# Arduino_Shield_RC_Controller.net
KiCad netlist of a schematic drawn in EAGLE
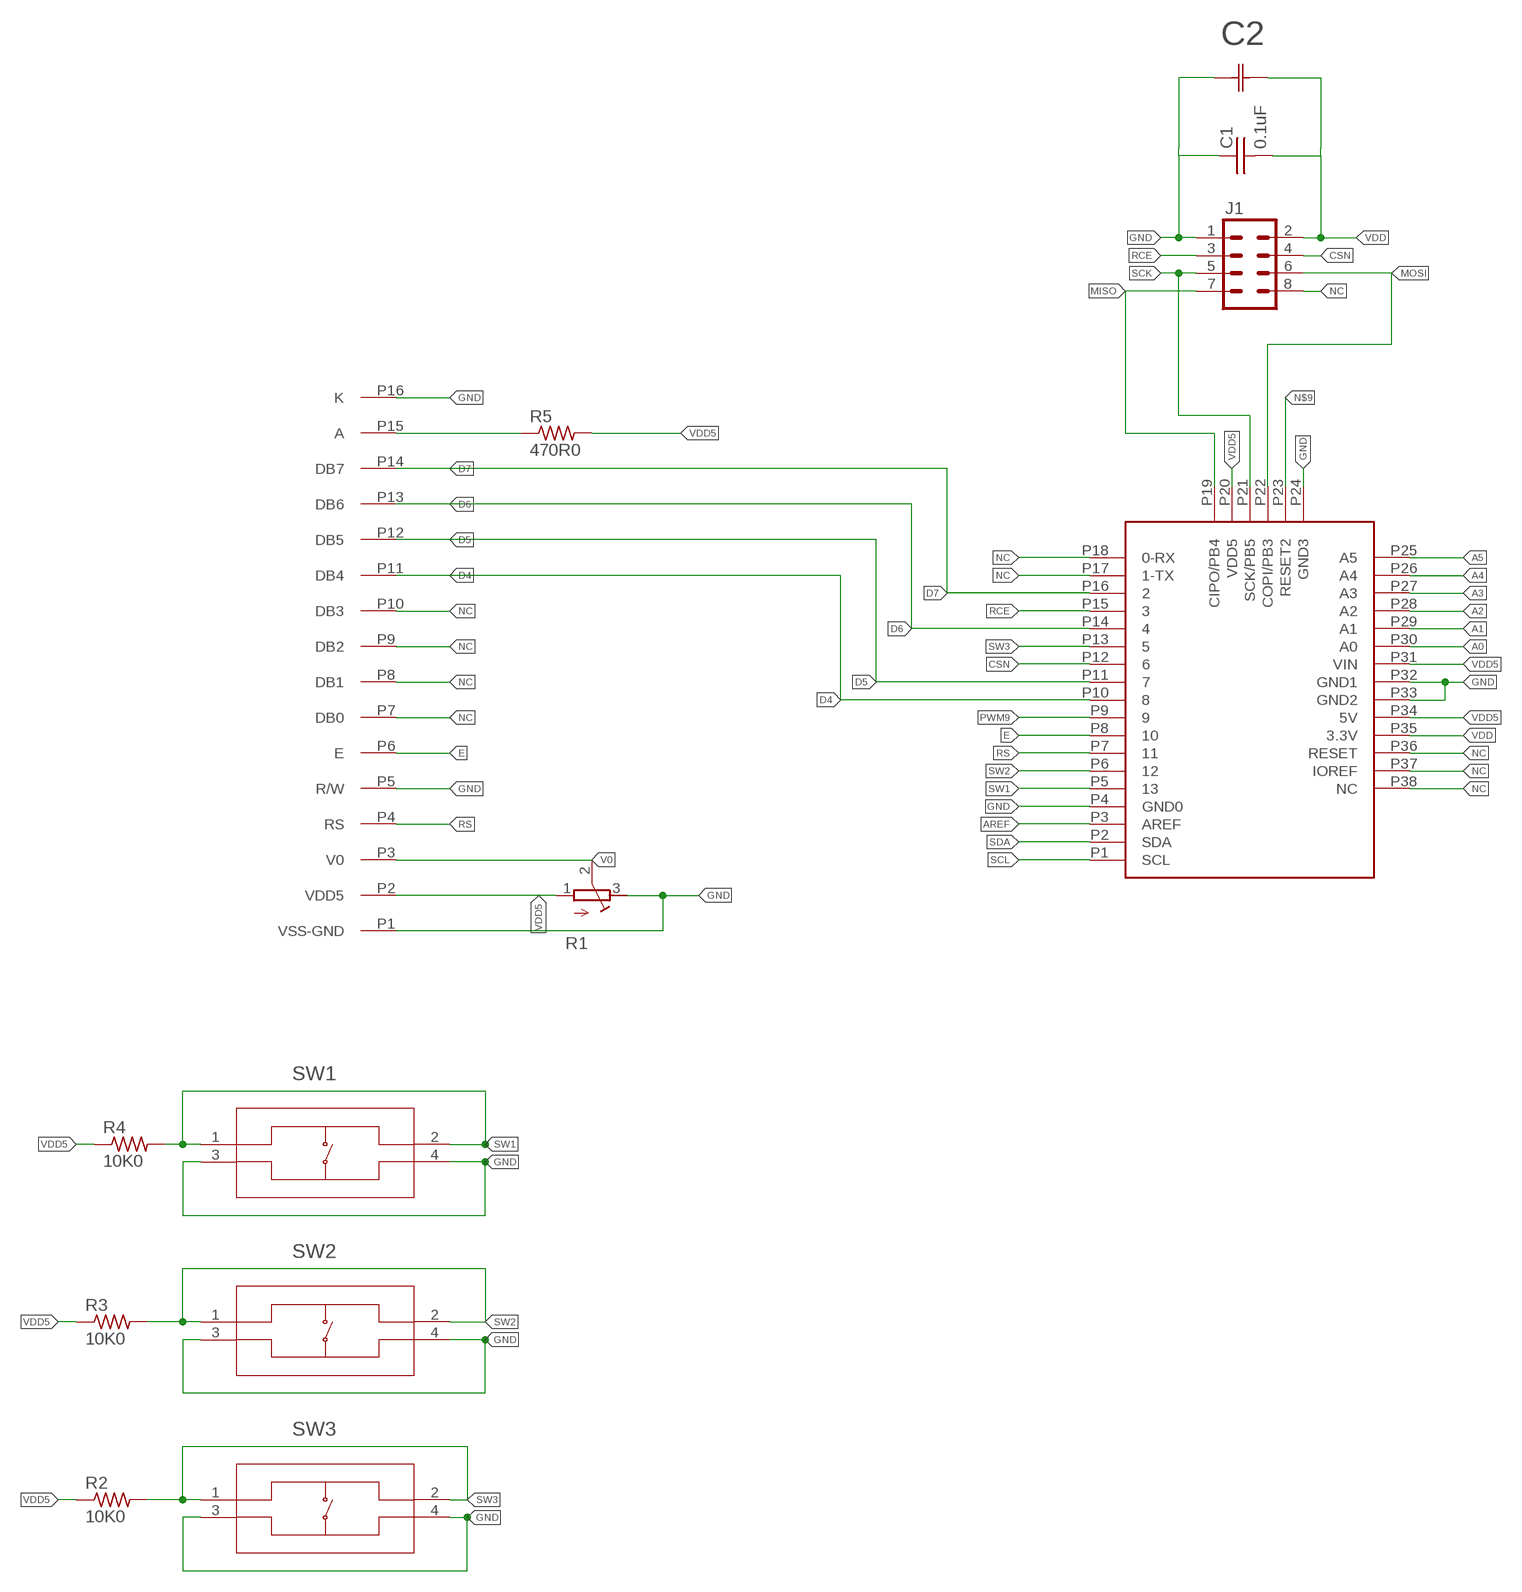
[diagram p0: schematic, sheet 1]

(export (version "E")
  (design (tool "Eeschema 10.0.6"))
  (components
    (comp (ref "AR1")
      (value "ARDUINO_R3")
      (footprint "eagle-import:ARDUINO_R3")
      (libsource (lib "eagle-import") (part "ARDUINO_R3"))
    )
    (comp (ref "C1")
      (value "0.1uF")
      (footprint "eagle-import:0402")
      (fields (field (name "PARTNO") "CL05F104ZO5NNNC"))
      (libsource (lib "eagle-import") (part "C_0402_0.1UF"))
    )
    (comp (ref "C2")
      (value "CAP_470UF_RAD_TH")
      (footprint "eagle-import:CAP_YX_10X16_RUB")
      (fields
        (field (name "MANUFACTURER_PART_NUMBER") "35ZLH470MEFC10X16")
        (field (name "COPYRIGHT") "Copyright (C) 2023 Ultra Librarian. All rights reserved.")
      )
      (libsource (lib "eagle-import") (part "CAP_470UF_RAD_TH"))
    )
    (comp (ref "J1")
      (value "CONN_04X2")
      (footprint "eagle-import:2X4")
      (libsource (lib "eagle-import") (part "CONN_04X2"))
    )
    (comp (ref "LCD1")
      (value "ADM1602K")
      (footprint "eagle-import:ADM1602K")
      (libsource (lib "eagle-import") (part "ADM1602K"))
    )
    (comp (ref "R1")
      (value "R-TRIMM3103")
      (footprint "eagle-import:RTRIM3103")
      (libsource (lib "eagle-import") (part "R-TRIMM3103"))
    )
    (comp (ref "R2")
      (value "10K0")
      (footprint "eagle-import:0402")
      (fields (field (name "PARTNO") "RMCF0402JT10K0"))
      (libsource (lib "eagle-import") (part "R_0402_10K0"))
    )
    (comp (ref "R3")
      (value "10K0")
      (footprint "eagle-import:0402")
      (fields (field (name "PARTNO") "RMCF0402JT10K0"))
      (libsource (lib "eagle-import") (part "R_0402_10K0"))
    )
    (comp (ref "R4")
      (value "10K0")
      (footprint "eagle-import:0402")
      (fields (field (name "PARTNO") "RMCF0402JT10K0"))
      (libsource (lib "eagle-import") (part "R_0402_10K0"))
    )
    (comp (ref "R5")
      (value "470R0")
      (footprint "eagle-import:0402")
      (fields (field (name "PARTNO") "RMCF0402JT470R"))
      (libsource (lib "eagle-import") (part "R_0402_470R0"))
    )
    (comp (ref "SW1")
      (value "PTS810SJG250SMTRLFS")
      (footprint "eagle-import:PTS810")
      (fields (field (name "COPYRIGHT") "Copyright (C) 2018 Accelerated Designs. All rights reserved"))
      (libsource (lib "eagle-import") (part "PTS810SJG250SMTRLFS"))
    )
    (comp (ref "SW2")
      (value "PTS810SJG250SMTRLFS")
      (footprint "eagle-import:PTS810")
      (fields (field (name "COPYRIGHT") "Copyright (C) 2018 Accelerated Designs. All rights reserved"))
      (libsource (lib "eagle-import") (part "PTS810SJG250SMTRLFS"))
    )
    (comp (ref "SW3")
      (value "PTS810SJG250SMTRLFS")
      (footprint "eagle-import:PTS810")
      (fields (field (name "COPYRIGHT") "Copyright (C) 2018 Accelerated Designs. All rights reserved"))
      (libsource (lib "eagle-import") (part "PTS810SJG250SMTRLFS"))
    )
  )
  (nets
    (net (code "1") (name "A0") (class "Default")
      (node (ref "AR1") (pin "P30") (pinfunction "A0_P30") (pintype "bidirectional"))
    )
    (net (code "2") (name "A1") (class "Default")
      (node (ref "AR1") (pin "P29") (pinfunction "A1_P29") (pintype "bidirectional"))
    )
    (net (code "3") (name "A2") (class "Default")
      (node (ref "AR1") (pin "P28") (pinfunction "A2_P28") (pintype "bidirectional"))
    )
    (net (code "4") (name "A3") (class "Default")
      (node (ref "AR1") (pin "P27") (pinfunction "A3_P27") (pintype "bidirectional"))
    )
    (net (code "5") (name "A4") (class "Default")
      (node (ref "AR1") (pin "P26") (pinfunction "A4_P26") (pintype "bidirectional"))
    )
    (net (code "6") (name "A5") (class "Default")
      (node (ref "AR1") (pin "P25") (pinfunction "A5_P25") (pintype "bidirectional"))
    )
    (net (code "7") (name "AREF") (class "Default")
      (node (ref "AR1") (pin "P3") (pinfunction "AREF_P3") (pintype "bidirectional"))
    )
    (net (code "8") (name "CSN") (class "Default")
      (node (ref "AR1") (pin "P12") (pinfunction "6_P12") (pintype "bidirectional"))
      (node (ref "J1") (pin "4") (pinfunction "4_4") (pintype "passive"))
    )
    (net (code "9") (name "D4") (class "Default")
      (node (ref "AR1") (pin "P10") (pinfunction "8_P10") (pintype "bidirectional"))
      (node (ref "LCD1") (pin "P11") (pinfunction "DB4_P11") (pintype "bidirectional"))
    )
    (net (code "10") (name "D5") (class "Default")
      (node (ref "AR1") (pin "P11") (pinfunction "7_P11") (pintype "bidirectional"))
      (node (ref "LCD1") (pin "P12") (pinfunction "DB5_P12") (pintype "bidirectional"))
    )
    (net (code "11") (name "D6") (class "Default")
      (node (ref "AR1") (pin "P14") (pinfunction "4_P14") (pintype "bidirectional"))
      (node (ref "LCD1") (pin "P13") (pinfunction "DB6_P13") (pintype "bidirectional"))
    )
    (net (code "12") (name "D7") (class "Default")
      (node (ref "AR1") (pin "P16") (pinfunction "2_P16") (pintype "bidirectional"))
      (node (ref "LCD1") (pin "P14") (pinfunction "DB7_P14") (pintype "bidirectional"))
    )
    (net (code "13") (name "E") (class "Default")
      (node (ref "AR1") (pin "P8") (pinfunction "10_P8") (pintype "bidirectional"))
      (node (ref "LCD1") (pin "P6") (pinfunction "E_P6") (pintype "bidirectional"))
    )
    (net (code "14") (name "GND") (class "Default")
      (node (ref "AR1") (pin "P24") (pinfunction "GND3_P24") (pintype "bidirectional"))
      (node (ref "AR1") (pin "P32") (pinfunction "GND1_P32") (pintype "bidirectional"))
      (node (ref "AR1") (pin "P33") (pinfunction "GND2_P33") (pintype "bidirectional"))
      (node (ref "AR1") (pin "P4") (pinfunction "GND0_P4") (pintype "bidirectional"))
      (node (ref "C1") (pin "P$1") (pinfunction "1_P$1") (pintype "passive"))
      (node (ref "C2") (pin "1") (pinfunction "1_1") (pintype "passive"))
      (node (ref "J1") (pin "1") (pinfunction "1_1") (pintype "passive"))
      (node (ref "LCD1") (pin "P1") (pinfunction "VSS-GND_P1") (pintype "bidirectional"))
      (node (ref "LCD1") (pin "P16") (pinfunction "K_P16") (pintype "bidirectional"))
      (node (ref "LCD1") (pin "P5") (pinfunction "R/W_P5") (pintype "bidirectional"))
      (node (ref "R1") (pin "3") (pinfunction "E_3") (pintype "passive"))
      (node (ref "SW1") (pin "3") (pinfunction "3_3") (pintype "passive"))
      (node (ref "SW1") (pin "4") (pinfunction "4_4") (pintype "passive"))
      (node (ref "SW2") (pin "3") (pinfunction "3_3") (pintype "passive"))
      (node (ref "SW2") (pin "4") (pinfunction "4_4") (pintype "passive"))
      (node (ref "SW3") (pin "3") (pinfunction "3_3") (pintype "passive"))
      (node (ref "SW3") (pin "4") (pinfunction "4_4") (pintype "passive"))
    )
    (net (code "15") (name "MISO") (class "Default")
      (node (ref "AR1") (pin "P19") (pinfunction "CIPO/PB4_P19") (pintype "bidirectional"))
      (node (ref "J1") (pin "7") (pinfunction "7_7") (pintype "passive"))
    )
    (net (code "16") (name "MOSI") (class "Default")
      (node (ref "AR1") (pin "P22") (pinfunction "COPI/PB3_P22") (pintype "bidirectional"))
      (node (ref "J1") (pin "6") (pinfunction "6_6") (pintype "passive"))
    )
    (net (code "17") (name "N$9") (class "Default")
      (node (ref "AR1") (pin "P23") (pinfunction "RESET2_P23") (pintype "bidirectional"))
    )
    (net (code "18") (name "NC") (class "Default")
      (node (ref "AR1") (pin "P17") (pinfunction "1-TX_P17") (pintype "bidirectional"))
      (node (ref "AR1") (pin "P18") (pinfunction "0-RX_P18") (pintype "bidirectional"))
      (node (ref "AR1") (pin "P36") (pinfunction "RESET_P36") (pintype "bidirectional"))
      (node (ref "AR1") (pin "P37") (pinfunction "IOREF_P37") (pintype "bidirectional"))
      (node (ref "AR1") (pin "P38") (pinfunction "NC_P38") (pintype "bidirectional"))
      (node (ref "J1") (pin "8") (pinfunction "8_8") (pintype "passive"))
      (node (ref "LCD1") (pin "P10") (pinfunction "DB3_P10") (pintype "bidirectional"))
      (node (ref "LCD1") (pin "P7") (pinfunction "DB0_P7") (pintype "bidirectional"))
      (node (ref "LCD1") (pin "P8") (pinfunction "DB1_P8") (pintype "bidirectional"))
      (node (ref "LCD1") (pin "P9") (pinfunction "DB2_P9") (pintype "bidirectional"))
    )
    (net (code "19") (name "Net-(LCD1-A)") (class "Default")
      (node (ref "LCD1") (pin "P15") (pinfunction "A_P15") (pintype "bidirectional"))
      (node (ref "R5") (pin "P$1") (pinfunction "1_P$1") (pintype "passive"))
    )
    (net (code "20") (name "PWM9") (class "Default")
      (node (ref "AR1") (pin "P9") (pinfunction "9_P9") (pintype "bidirectional"))
    )
    (net (code "21") (name "RCE") (class "Default")
      (node (ref "AR1") (pin "P15") (pinfunction "3_P15") (pintype "bidirectional"))
      (node (ref "J1") (pin "3") (pinfunction "3_3") (pintype "passive"))
    )
    (net (code "22") (name "RS") (class "Default")
      (node (ref "AR1") (pin "P7") (pinfunction "11_P7") (pintype "bidirectional"))
      (node (ref "LCD1") (pin "P4") (pinfunction "RS_P4") (pintype "bidirectional"))
    )
    (net (code "23") (name "SCK") (class "Default")
      (node (ref "AR1") (pin "P21") (pinfunction "SCK/PB5_P21") (pintype "bidirectional"))
      (node (ref "J1") (pin "5") (pinfunction "5_5") (pintype "passive"))
    )
    (net (code "24") (name "SCL") (class "Default")
      (node (ref "AR1") (pin "P1") (pinfunction "SCL_P1") (pintype "bidirectional"))
    )
    (net (code "25") (name "SDA") (class "Default")
      (node (ref "AR1") (pin "P2") (pinfunction "SDA_P2") (pintype "bidirectional"))
    )
    (net (code "26") (name "SW1") (class "Default")
      (node (ref "AR1") (pin "P5") (pinfunction "13_P5") (pintype "bidirectional"))
      (node (ref "R4") (pin "P$2") (pinfunction "2_P$2") (pintype "passive"))
      (node (ref "SW1") (pin "1") (pinfunction "1_1") (pintype "passive"))
      (node (ref "SW1") (pin "2") (pinfunction "2_2") (pintype "passive"))
    )
    (net (code "27") (name "SW2") (class "Default")
      (node (ref "AR1") (pin "P6") (pinfunction "12_P6") (pintype "bidirectional"))
      (node (ref "R3") (pin "P$2") (pinfunction "2_P$2") (pintype "passive"))
      (node (ref "SW2") (pin "1") (pinfunction "1_1") (pintype "passive"))
      (node (ref "SW2") (pin "2") (pinfunction "2_2") (pintype "passive"))
    )
    (net (code "28") (name "SW3") (class "Default")
      (node (ref "AR1") (pin "P13") (pinfunction "5_P13") (pintype "bidirectional"))
      (node (ref "R2") (pin "P$2") (pinfunction "2_P$2") (pintype "passive"))
      (node (ref "SW3") (pin "1") (pinfunction "1_1") (pintype "passive"))
      (node (ref "SW3") (pin "2") (pinfunction "2_2") (pintype "passive"))
    )
    (net (code "29") (name "V0") (class "Default")
      (node (ref "LCD1") (pin "P3") (pinfunction "V0_P3") (pintype "bidirectional"))
      (node (ref "R1") (pin "2") (pinfunction "S_2") (pintype "passive"))
    )
    (net (code "30") (name "VDD") (class "Default")
      (node (ref "AR1") (pin "P35") (pinfunction "3.3V_P35") (pintype "bidirectional"))
      (node (ref "C1") (pin "P$2") (pinfunction "2_P$2") (pintype "passive"))
      (node (ref "C2") (pin "2") (pinfunction "2_2") (pintype "passive"))
      (node (ref "J1") (pin "2") (pinfunction "2_2") (pintype "passive"))
    )
    (net (code "31") (name "VDD5") (class "Default")
      (node (ref "AR1") (pin "P20") (pinfunction "VDD5_P20") (pintype "bidirectional"))
      (node (ref "AR1") (pin "P31") (pinfunction "VIN_P31") (pintype "bidirectional"))
      (node (ref "AR1") (pin "P34") (pinfunction "5V_P34") (pintype "bidirectional"))
      (node (ref "LCD1") (pin "P2") (pinfunction "VDD5_P2") (pintype "bidirectional"))
      (node (ref "R1") (pin "1") (pinfunction "A_1") (pintype "passive"))
      (node (ref "R2") (pin "P$1") (pinfunction "1_P$1") (pintype "passive"))
      (node (ref "R3") (pin "P$1") (pinfunction "1_P$1") (pintype "passive"))
      (node (ref "R4") (pin "P$1") (pinfunction "1_P$1") (pintype "passive"))
      (node (ref "R5") (pin "P$2") (pinfunction "2_P$2") (pintype "passive"))
    )
  )
)
